# vusbtinyisp_smt_voltage_reg.net
KiCad netlist of a schematic drawn in EAGLE
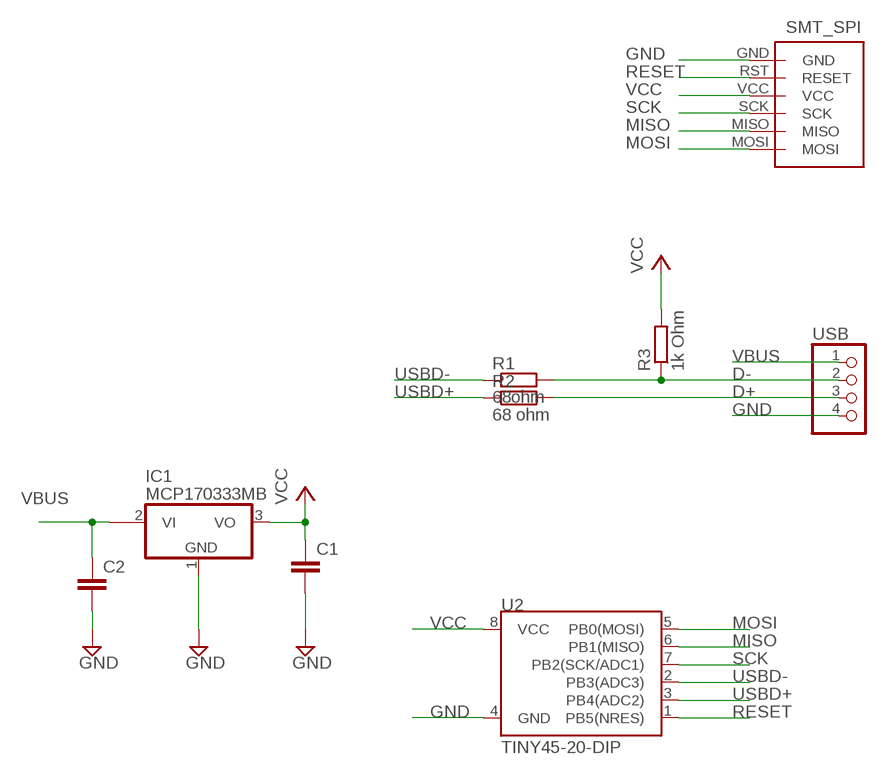
[diagram p0: schematic, sheet 1]

(export (version "E")
  (design (tool "Eeschema 10.0.6"))
  (components
    (comp (ref "C1")
      (value "CAP1206")
      (footprint "eagle-import:1206")
      (libsource (lib "eagle-import") (part "CAP1206"))
    )
    (comp (ref "C2")
      (value "CAP1206")
      (footprint "eagle-import:1206")
      (libsource (lib "eagle-import") (part "CAP1206"))
    )
    (comp (ref "IC1")
      (value "MCP170333MB")
      (footprint "eagle-import:SOT89")
      (libsource (lib "eagle-import") (part "MCP1703MB33"))
    )
    (comp (ref "R1")
      (value "68ohm")
      (footprint "eagle-import:R0805")
      (libsource (lib "eagle-import") (part "R-EU_R0805"))
    )
    (comp (ref "R2")
      (value "68 ohm")
      (footprint "eagle-import:R0805")
      (libsource (lib "eagle-import") (part "R-EU_R0805"))
    )
    (comp (ref "R3")
      (value "1k Ohm")
      (footprint "eagle-import:R1206")
      (libsource (lib "eagle-import") (part "R-EU_R1206"))
    )
    (comp (ref "U$1")
      (value "SMT_ISP")
      (footprint "eagle-import:SMT_PADS")
      (libsource (lib "eagle-import") (part "SMT_ISP"))
    )
    (comp (ref "U2")
      (value "TINY45-20-DIP")
      (footprint "eagle-import:DIP08")
      (libsource (lib "eagle-import") (part "ATTINY45TINY45-20-DIP"))
    )
    (comp (ref "USB")
      (value "PINHD-1X4")
      (footprint "eagle-import:1X04")
      (libsource (lib "eagle-import") (part "PINHD-1X4"))
    )
  )
  (nets
    (net (code "1") (name "/D+") (class "Default")
      (node (ref "R2") (pin "2") (pinfunction "2_2") (pintype "passive"))
      (node (ref "USB") (pin "3") (pinfunction "3_3") (pintype "passive"))
    )
    (net (code "2") (name "/D-") (class "Default")
      (node (ref "R1") (pin "2") (pinfunction "2_2") (pintype "passive"))
      (node (ref "R3") (pin "1") (pinfunction "1_1") (pintype "passive"))
      (node (ref "USB") (pin "2") (pinfunction "2_2") (pintype "passive"))
    )
    (net (code "3") (name "/MISO") (class "Default")
      (node (ref "U$1") (pin "MISO") (pinfunction "MISO_MISO") (pintype "bidirectional"))
      (node (ref "U2") (pin "6") (pinfunction "PB1(MISO)_6") (pintype "bidirectional"))
    )
    (net (code "4") (name "/MOSI") (class "Default")
      (node (ref "U$1") (pin "MOSI") (pinfunction "MOSI_MOSI") (pintype "bidirectional"))
      (node (ref "U2") (pin "5") (pinfunction "PB0(MOSI)_5") (pintype "bidirectional"))
    )
    (net (code "5") (name "/RESET") (class "Default")
      (node (ref "U$1") (pin "RST") (pinfunction "RESET_RST") (pintype "bidirectional"))
      (node (ref "U2") (pin "1") (pinfunction "PB5(NRES)_1") (pintype "bidirectional"))
    )
    (net (code "6") (name "/SCK") (class "Default")
      (node (ref "U$1") (pin "SCK") (pinfunction "SCK_SCK") (pintype "bidirectional"))
      (node (ref "U2") (pin "7") (pinfunction "PB2(SCK/ADC1)_7") (pintype "bidirectional"))
    )
    (net (code "7") (name "/USBD+") (class "Default")
      (node (ref "R2") (pin "1") (pinfunction "1_1") (pintype "passive"))
      (node (ref "U2") (pin "3") (pinfunction "PB4(ADC2)_3") (pintype "bidirectional"))
    )
    (net (code "8") (name "/USBD-") (class "Default")
      (node (ref "R1") (pin "1") (pinfunction "1_1") (pintype "passive"))
      (node (ref "U2") (pin "2") (pinfunction "PB3(ADC3)_2") (pintype "bidirectional"))
    )
    (net (code "9") (name "/VBUS") (class "Default")
      (node (ref "C2") (pin "1") (pinfunction "1_1") (pintype "passive"))
      (node (ref "IC1") (pin "2@1") (pinfunction "VI1_2@1") (pintype "input"))
      (node (ref "USB") (pin "1") (pinfunction "1_1") (pintype "passive"))
    )
    (net (code "10") (name "GND") (class "Default")
      (node (ref "C1") (pin "2") (pinfunction "2_2") (pintype "passive"))
      (node (ref "C2") (pin "2") (pinfunction "2_2") (pintype "passive"))
      (node (ref "IC1") (pin "1") (pinfunction "GND_1") (pintype "passive"))
      (node (ref "U$1") (pin "GND") (pinfunction "GND_GND") (pintype "bidirectional"))
      (node (ref "U2") (pin "4") (pinfunction "GND_4") (pintype "bidirectional"))
      (node (ref "USB") (pin "4") (pinfunction "4_4") (pintype "passive"))
    )
    (net (code "11") (name "VCC") (class "Default")
      (node (ref "C1") (pin "1") (pinfunction "1_1") (pintype "passive"))
      (node (ref "IC1") (pin "3") (pinfunction "VO_3") (pintype "passive"))
      (node (ref "R3") (pin "2") (pinfunction "2_2") (pintype "passive"))
      (node (ref "U$1") (pin "VCC") (pinfunction "VCC_VCC") (pintype "bidirectional"))
      (node (ref "U2") (pin "8") (pinfunction "VCC_8") (pintype "bidirectional"))
    )
    (net (code "12") (name "unconnected-(IC1-VI-Pad2)") (class "Default")
      (node (ref "IC1") (pin "2") (pinfunction "VI_2") (pintype "input"))
    )
  )
)
